# MEMORY.net
KiCad netlist of a schematic drawn in Altium Designer
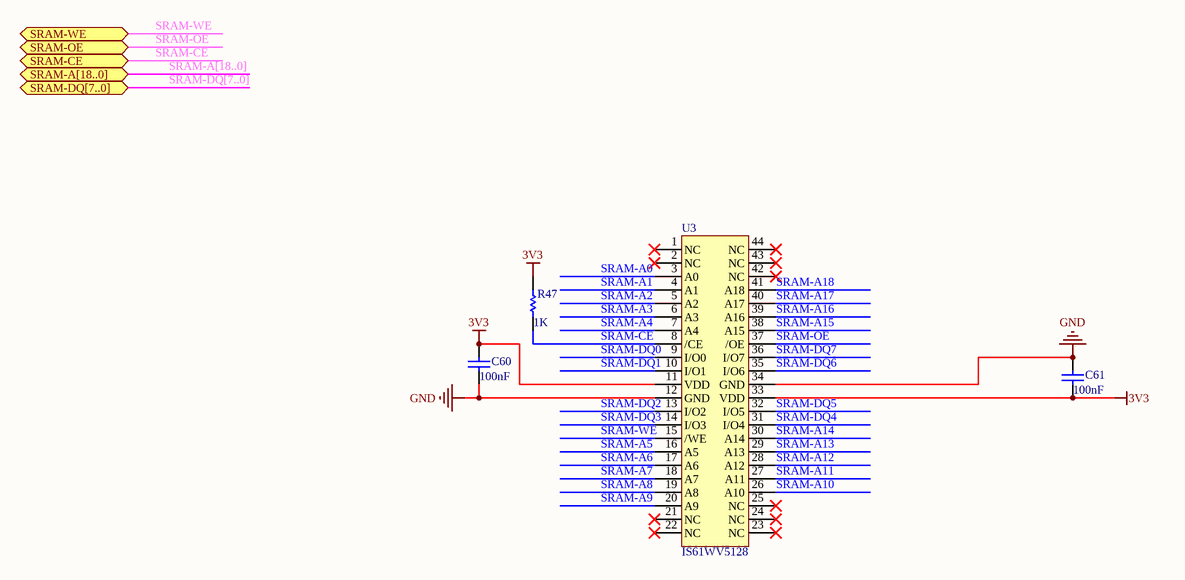
[diagram p0: MEMORY.SchDoc]

(export (version "E")
  (design (tool "Eeschema 10.0.6"))
  (components
    (comp (ref "C60")
      (value "100nF")
      (footprint "1608[0603]")
      (description "贴片电容")
      (fields (field (name "Comment") "Cap") (field (name "PUBLISHER") "Altium Limited"))
      (libsource (lib "Sparks") (part "Cap"))
    )
    (comp (ref "C61")
      (value "100nF")
      (footprint "1608[0603]")
      (description "贴片电容")
      (fields (field (name "Comment") "Cap") (field (name "PUBLISHER") "Altium Limited"))
      (libsource (lib "Sparks") (part "Cap"))
    )
    (comp (ref "R47")
      (value "1K")
      (footprint "1608[0603]")
      (description "贴片电阻")
      (fields (field (name "Comment") "Res") (field (name "PUBLISHER") "Altium Limited"))
      (libsource (lib "Sparks") (part "Res"))
    )
    (comp (ref "U3")
      (value "IS61WV5128")
      (footprint "SOP127P600-8N IS61WV5128")
      (libsource (lib "2号库") (part "IS61WV5128"))
    )
  )
  (nets
    (net (code "1") (name "/SRAM-A0") (class "Default")
      (node (ref "U3") (pin "3") (pinfunction "A0_3") (pintype "passive"))
    )
    (net (code "2") (name "/SRAM-A1") (class "Default")
      (node (ref "U3") (pin "4") (pinfunction "A1_4") (pintype "passive"))
    )
    (net (code "3") (name "/SRAM-A2") (class "Default")
      (node (ref "U3") (pin "5") (pinfunction "A2_5") (pintype "passive"))
    )
    (net (code "4") (name "/SRAM-A3") (class "Default")
      (node (ref "U3") (pin "6") (pinfunction "A3_6") (pintype "passive"))
    )
    (net (code "5") (name "/SRAM-A4") (class "Default")
      (node (ref "U3") (pin "7") (pinfunction "A4_7") (pintype "passive"))
    )
    (net (code "6") (name "/SRAM-A5") (class "Default")
      (node (ref "U3") (pin "16") (pinfunction "A5_16") (pintype "passive"))
    )
    (net (code "7") (name "/SRAM-A6") (class "Default")
      (node (ref "U3") (pin "17") (pinfunction "A6_17") (pintype "passive"))
    )
    (net (code "8") (name "/SRAM-A7") (class "Default")
      (node (ref "U3") (pin "18") (pinfunction "A7_18") (pintype "passive"))
    )
    (net (code "9") (name "/SRAM-A8") (class "Default")
      (node (ref "U3") (pin "19") (pinfunction "A8_19") (pintype "passive"))
    )
    (net (code "10") (name "/SRAM-A9") (class "Default")
      (node (ref "U3") (pin "20") (pinfunction "A9_20") (pintype "passive"))
    )
    (net (code "11") (name "/SRAM-A10") (class "Default")
      (node (ref "U3") (pin "26") (pinfunction "A10_26") (pintype "passive"))
    )
    (net (code "12") (name "/SRAM-A11") (class "Default")
      (node (ref "U3") (pin "27") (pinfunction "A11_27") (pintype "passive"))
    )
    (net (code "13") (name "/SRAM-A12") (class "Default")
      (node (ref "U3") (pin "28") (pinfunction "A12_28") (pintype "passive"))
    )
    (net (code "14") (name "/SRAM-A13") (class "Default")
      (node (ref "U3") (pin "29") (pinfunction "A13_29") (pintype "passive"))
    )
    (net (code "15") (name "/SRAM-A14") (class "Default")
      (node (ref "U3") (pin "30") (pinfunction "A14_30") (pintype "passive"))
    )
    (net (code "16") (name "/SRAM-A15") (class "Default")
      (node (ref "U3") (pin "38") (pinfunction "A15_38") (pintype "passive"))
    )
    (net (code "17") (name "/SRAM-A16") (class "Default")
      (node (ref "U3") (pin "39") (pinfunction "A16_39") (pintype "passive"))
    )
    (net (code "18") (name "/SRAM-A17") (class "Default")
      (node (ref "U3") (pin "40") (pinfunction "A17_40") (pintype "passive"))
    )
    (net (code "19") (name "/SRAM-A18") (class "Default")
      (node (ref "U3") (pin "41") (pinfunction "A18_41") (pintype "passive"))
    )
    (net (code "21") (name "/SRAM-CE") (class "Default")
      (node (ref "R47") (pin "1") (pinfunction "1_1") (pintype "passive"))
      (node (ref "U3") (pin "8") (pinfunction "/CE_8") (pintype "passive"))
    )
    (net (code "22") (name "/SRAM-DQ0") (class "Default")
      (node (ref "U3") (pin "9") (pinfunction "I/O0_9") (pintype "passive"))
    )
    (net (code "23") (name "/SRAM-DQ1") (class "Default")
      (node (ref "U3") (pin "10") (pinfunction "I/O1_10") (pintype "passive"))
    )
    (net (code "24") (name "/SRAM-DQ2") (class "Default")
      (node (ref "U3") (pin "13") (pinfunction "I/O2_13") (pintype "passive"))
    )
    (net (code "25") (name "/SRAM-DQ3") (class "Default")
      (node (ref "U3") (pin "14") (pinfunction "I/O3_14") (pintype "passive"))
    )
    (net (code "26") (name "/SRAM-DQ4") (class "Default")
      (node (ref "U3") (pin "31") (pinfunction "I/O4_31") (pintype "passive"))
    )
    (net (code "27") (name "/SRAM-DQ5") (class "Default")
      (node (ref "U3") (pin "32") (pinfunction "I/O5_32") (pintype "passive"))
    )
    (net (code "28") (name "/SRAM-DQ6") (class "Default")
      (node (ref "U3") (pin "35") (pinfunction "I/O6_35") (pintype "passive"))
    )
    (net (code "29") (name "/SRAM-DQ7") (class "Default")
      (node (ref "U3") (pin "36") (pinfunction "I/O7_36") (pintype "passive"))
    )
    (net (code "31") (name "/SRAM-OE") (class "Default")
      (node (ref "U3") (pin "37") (pinfunction "/OE_37") (pintype "passive"))
    )
    (net (code "32") (name "/SRAM-WE") (class "Default")
      (node (ref "U3") (pin "15") (pinfunction "/WE_15") (pintype "passive"))
    )
    (net (code "33") (name "3V3") (class "Default")
      (node (ref "C60") (pin "2") (pinfunction "2_2") (pintype "passive"))
      (node (ref "C61") (pin "1") (pinfunction "1_1") (pintype "passive"))
      (node (ref "R47") (pin "2") (pinfunction "2_2") (pintype "passive"))
      (node (ref "U3") (pin "11") (pinfunction "VDD_11") (pintype "passive"))
      (node (ref "U3") (pin "33") (pinfunction "VDD_33") (pintype "passive"))
    )
    (net (code "34") (name "GND") (class "Default")
      (node (ref "C60") (pin "1") (pinfunction "1_1") (pintype "passive"))
      (node (ref "C61") (pin "2") (pinfunction "2_2") (pintype "passive"))
      (node (ref "U3") (pin "12") (pinfunction "GND_12") (pintype "passive"))
      (node (ref "U3") (pin "34") (pinfunction "GND_34") (pintype "passive"))
    )
    (net (code "35") (name "unconnected-(U3-NC-Pad1)") (class "Default")
      (node (ref "U3") (pin "1") (pinfunction "NC_1") (pintype "passive+no_connect"))
    )
    (net (code "36") (name "unconnected-(U3-NC-Pad2)") (class "Default")
      (node (ref "U3") (pin "2") (pinfunction "NC_2") (pintype "passive+no_connect"))
    )
    (net (code "37") (name "unconnected-(U3-NC-Pad21)") (class "Default")
      (node (ref "U3") (pin "21") (pinfunction "NC_21") (pintype "passive+no_connect"))
    )
    (net (code "38") (name "unconnected-(U3-NC-Pad22)") (class "Default")
      (node (ref "U3") (pin "22") (pinfunction "NC_22") (pintype "passive+no_connect"))
    )
    (net (code "39") (name "unconnected-(U3-NC-Pad23)") (class "Default")
      (node (ref "U3") (pin "23") (pinfunction "NC_23") (pintype "passive+no_connect"))
    )
    (net (code "40") (name "unconnected-(U3-NC-Pad24)") (class "Default")
      (node (ref "U3") (pin "24") (pinfunction "NC_24") (pintype "passive+no_connect"))
    )
    (net (code "41") (name "unconnected-(U3-NC-Pad25)") (class "Default")
      (node (ref "U3") (pin "25") (pinfunction "NC_25") (pintype "passive+no_connect"))
    )
    (net (code "42") (name "unconnected-(U3-NC-Pad42)") (class "Default")
      (node (ref "U3") (pin "42") (pinfunction "NC_42") (pintype "passive+no_connect"))
    )
    (net (code "43") (name "unconnected-(U3-NC-Pad43)") (class "Default")
      (node (ref "U3") (pin "43") (pinfunction "NC_43") (pintype "passive+no_connect"))
    )
    (net (code "44") (name "unconnected-(U3-NC-Pad44)") (class "Default")
      (node (ref "U3") (pin "44") (pinfunction "NC_44") (pintype "passive+no_connect"))
    )
  )
)
